# NOT.net
KiCad netlist of a schematic drawn in EAGLE
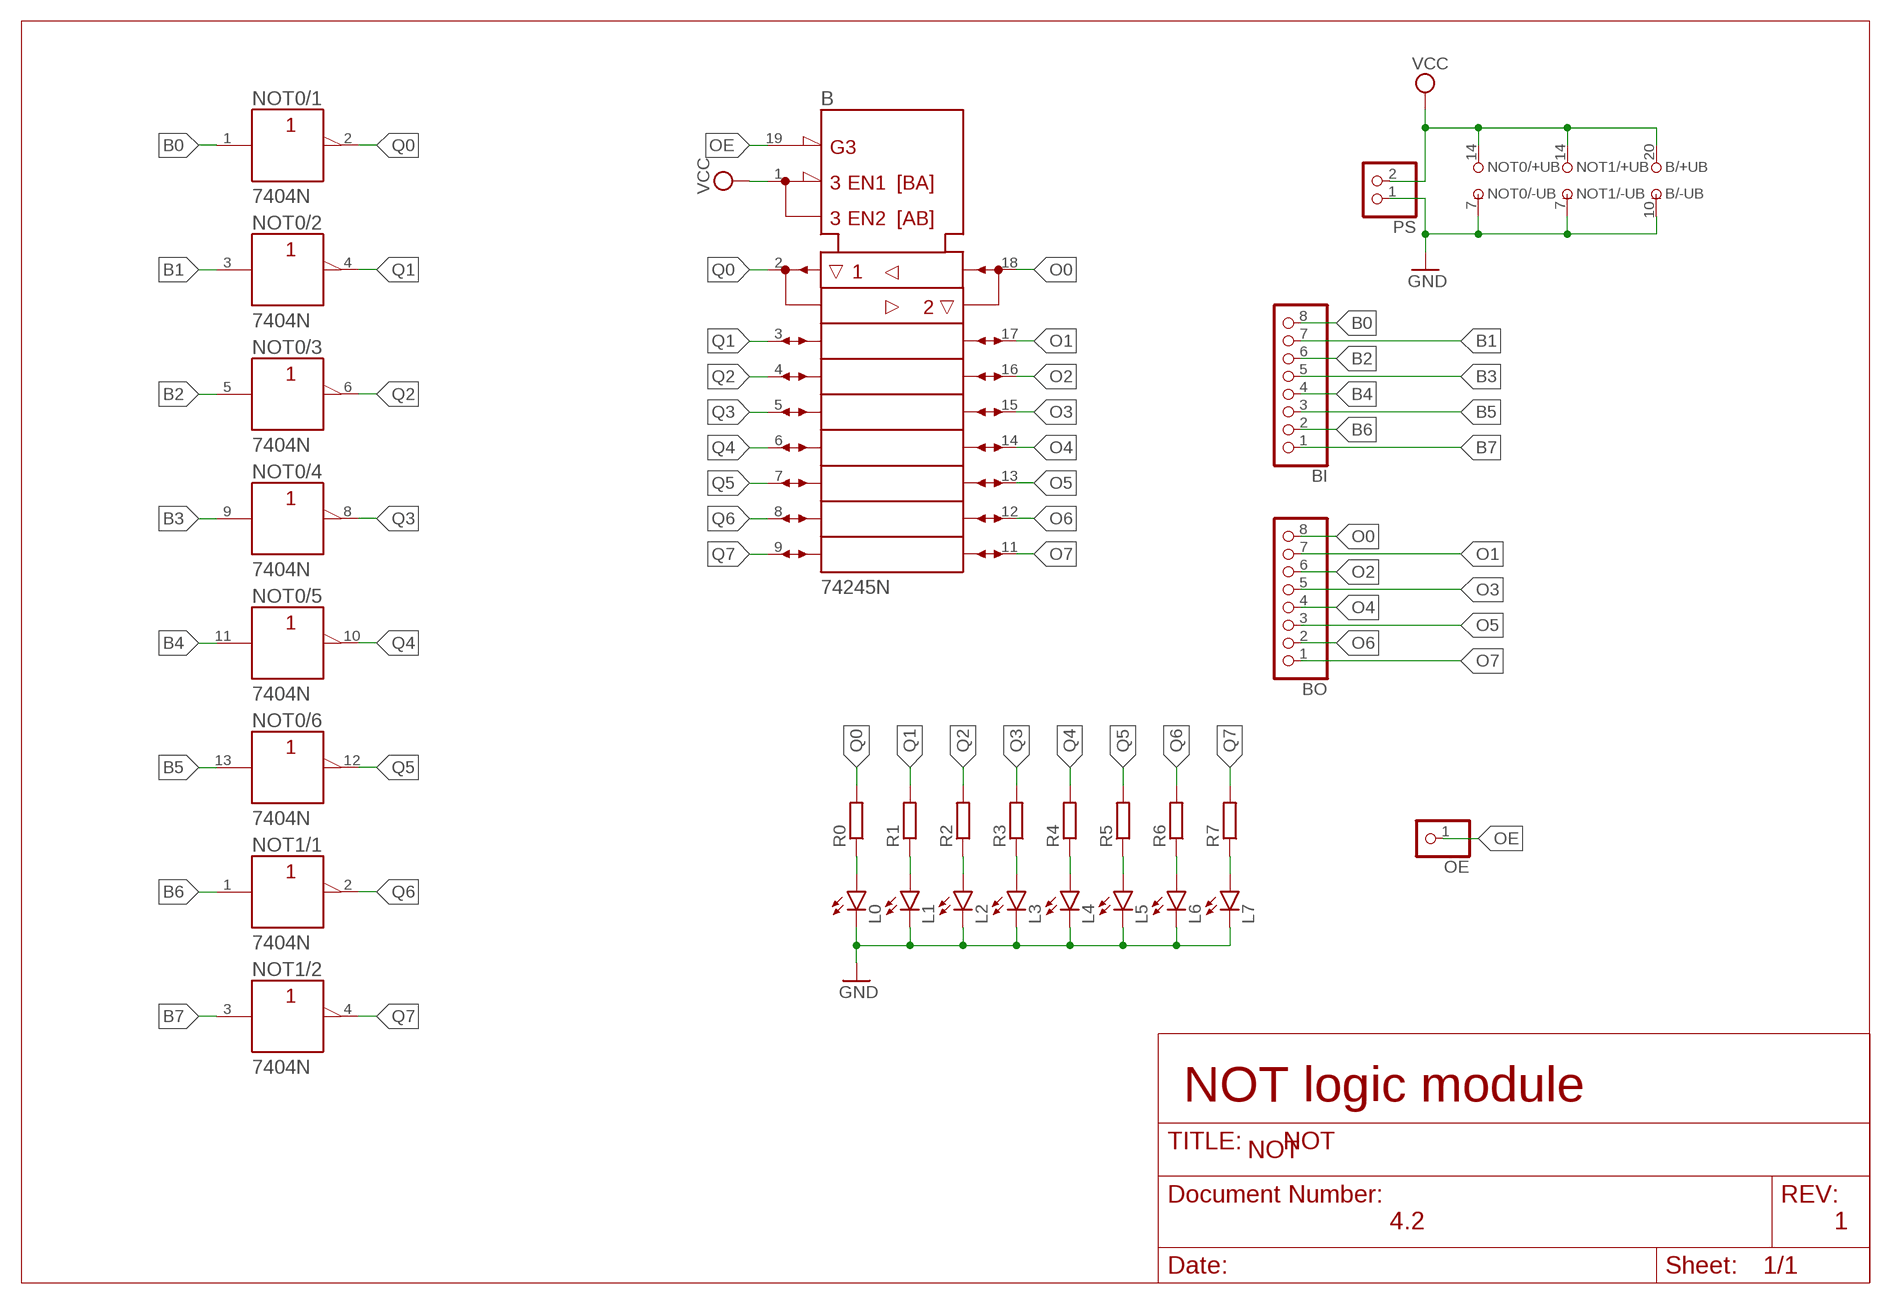
[diagram p0: schematic, sheet 1]

(export (version "E")
  (design (tool "Eeschema 10.0.6"))
  (components
    (comp (ref "B")
      (value "74245N")
      (footprint "eagle-import:DIL20")
      (libsource (lib "eagle-import") (part "74245N"))
    )
    (comp (ref "BI")
      (value "PINHD-1X8")
      (footprint "eagle-import:1X08")
      (libsource (lib "eagle-import") (part "PINHD-1X8"))
    )
    (comp (ref "BO")
      (value "PINHD-1X8")
      (footprint "eagle-import:1X08")
      (libsource (lib "eagle-import") (part "PINHD-1X8"))
    )
    (comp (ref "L0")
      (value "LED5MM")
      (footprint "eagle-import:LED5MM")
      (libsource (lib "eagle-import") (part "LED5MM"))
    )
    (comp (ref "L1")
      (value "LED5MM")
      (footprint "eagle-import:LED5MM")
      (libsource (lib "eagle-import") (part "LED5MM"))
    )
    (comp (ref "L2")
      (value "LED5MM")
      (footprint "eagle-import:LED5MM")
      (libsource (lib "eagle-import") (part "LED5MM"))
    )
    (comp (ref "L3")
      (value "LED5MM")
      (footprint "eagle-import:LED5MM")
      (libsource (lib "eagle-import") (part "LED5MM"))
    )
    (comp (ref "L4")
      (value "LED5MM")
      (footprint "eagle-import:LED5MM")
      (libsource (lib "eagle-import") (part "LED5MM"))
    )
    (comp (ref "L5")
      (value "LED5MM")
      (footprint "eagle-import:LED5MM")
      (libsource (lib "eagle-import") (part "LED5MM"))
    )
    (comp (ref "L6")
      (value "LED5MM")
      (footprint "eagle-import:LED5MM")
      (libsource (lib "eagle-import") (part "LED5MM"))
    )
    (comp (ref "L7")
      (value "LED5MM")
      (footprint "eagle-import:LED5MM")
      (libsource (lib "eagle-import") (part "LED5MM"))
    )
    (comp (ref "NOT0")
      (value "7404N")
      (footprint "eagle-import:DIL14")
      (libsource (lib "eagle-import") (part "7404N"))
    )
    (comp (ref "NOT1")
      (value "7404N")
      (footprint "eagle-import:DIL14")
      (libsource (lib "eagle-import") (part "7404N"))
    )
    (comp (ref "OE")
      (value "PINHD-1X1")
      (footprint "eagle-import:1X01")
      (libsource (lib "eagle-import") (part "PINHD-1X1"))
    )
    (comp (ref "PS")
      (value "PINHD-1X2")
      (footprint "eagle-import:1X02")
      (libsource (lib "eagle-import") (part "PINHD-1X2"))
    )
    (comp (ref "R0")
      (value "R-EU_0204/7")
      (footprint "eagle-import:0204_7")
      (libsource (lib "eagle-import") (part "R-EU_0204/7"))
    )
    (comp (ref "R1")
      (value "R-EU_0204/7")
      (footprint "eagle-import:0204_7")
      (libsource (lib "eagle-import") (part "R-EU_0204/7"))
    )
    (comp (ref "R2")
      (value "R-EU_0204/7")
      (footprint "eagle-import:0204_7")
      (libsource (lib "eagle-import") (part "R-EU_0204/7"))
    )
    (comp (ref "R3")
      (value "R-EU_0204/7")
      (footprint "eagle-import:0204_7")
      (libsource (lib "eagle-import") (part "R-EU_0204/7"))
    )
    (comp (ref "R4")
      (value "R-EU_0204/7")
      (footprint "eagle-import:0204_7")
      (libsource (lib "eagle-import") (part "R-EU_0204/7"))
    )
    (comp (ref "R5")
      (value "R-EU_0204/7")
      (footprint "eagle-import:0204_7")
      (libsource (lib "eagle-import") (part "R-EU_0204/7"))
    )
    (comp (ref "R6")
      (value "R-EU_0204/7")
      (footprint "eagle-import:0204_7")
      (libsource (lib "eagle-import") (part "R-EU_0204/7"))
    )
    (comp (ref "R7")
      (value "R-EU_0204/7")
      (footprint "eagle-import:0204_7")
      (libsource (lib "eagle-import") (part "R-EU_0204/7"))
    )
  )
  (nets
    (net (code "1") (name "B0") (class "Default")
      (node (ref "BI") (pin "8") (pinfunction "8_8") (pintype "passive"))
      (node (ref "NOT0") (pin "1") (pinfunction "A_1") (pintype "input"))
    )
    (net (code "2") (name "B1") (class "Default")
      (node (ref "BI") (pin "7") (pinfunction "7_7") (pintype "passive"))
      (node (ref "NOT0") (pin "3") (pinfunction "A_3") (pintype "input"))
    )
    (net (code "3") (name "B2") (class "Default")
      (node (ref "BI") (pin "6") (pinfunction "6_6") (pintype "passive"))
      (node (ref "NOT0") (pin "5") (pinfunction "A_5") (pintype "input"))
    )
    (net (code "4") (name "B3") (class "Default")
      (node (ref "BI") (pin "5") (pinfunction "5_5") (pintype "passive"))
      (node (ref "NOT0") (pin "9") (pinfunction "A_9") (pintype "input"))
    )
    (net (code "5") (name "B4") (class "Default")
      (node (ref "BI") (pin "4") (pinfunction "4_4") (pintype "passive"))
      (node (ref "NOT0") (pin "11") (pinfunction "A_11") (pintype "input"))
    )
    (net (code "6") (name "B5") (class "Default")
      (node (ref "BI") (pin "3") (pinfunction "3_3") (pintype "passive"))
      (node (ref "NOT0") (pin "13") (pinfunction "A_13") (pintype "input"))
    )
    (net (code "7") (name "B6") (class "Default")
      (node (ref "BI") (pin "2") (pinfunction "2_2") (pintype "passive"))
      (node (ref "NOT1") (pin "1") (pinfunction "A_1") (pintype "input"))
    )
    (net (code "8") (name "B7") (class "Default")
      (node (ref "BI") (pin "1") (pinfunction "1_1") (pintype "passive"))
      (node (ref "NOT1") (pin "3") (pinfunction "A_3") (pintype "input"))
    )
    (net (code "9") (name "GND") (class "Default")
      (node (ref "B") (pin "10") (pinfunction "-UB_10") (pintype "power_in"))
      (node (ref "L0") (pin "K") (pinfunction "C_K") (pintype "passive"))
      (node (ref "L1") (pin "K") (pinfunction "C_K") (pintype "passive"))
      (node (ref "L2") (pin "K") (pinfunction "C_K") (pintype "passive"))
      (node (ref "L3") (pin "K") (pinfunction "C_K") (pintype "passive"))
      (node (ref "L4") (pin "K") (pinfunction "C_K") (pintype "passive"))
      (node (ref "L5") (pin "K") (pinfunction "C_K") (pintype "passive"))
      (node (ref "L6") (pin "K") (pinfunction "C_K") (pintype "passive"))
      (node (ref "L7") (pin "K") (pinfunction "C_K") (pintype "passive"))
      (node (ref "NOT0") (pin "7") (pinfunction "-UB_7") (pintype "power_in"))
      (node (ref "NOT1") (pin "7") (pinfunction "-UB_7") (pintype "power_in"))
      (node (ref "PS") (pin "1") (pinfunction "1_1") (pintype "passive"))
    )
    (net (code "10") (name "Net-(L0-PadA)") (class "Default")
      (node (ref "L0") (pin "A") (pinfunction "A_A") (pintype "passive"))
      (node (ref "R0") (pin "1") (pinfunction "1_1") (pintype "passive"))
    )
    (net (code "11") (name "Net-(L1-PadA)") (class "Default")
      (node (ref "L1") (pin "A") (pinfunction "A_A") (pintype "passive"))
      (node (ref "R1") (pin "1") (pinfunction "1_1") (pintype "passive"))
    )
    (net (code "12") (name "Net-(L2-PadA)") (class "Default")
      (node (ref "L2") (pin "A") (pinfunction "A_A") (pintype "passive"))
      (node (ref "R2") (pin "1") (pinfunction "1_1") (pintype "passive"))
    )
    (net (code "13") (name "Net-(L3-PadA)") (class "Default")
      (node (ref "L3") (pin "A") (pinfunction "A_A") (pintype "passive"))
      (node (ref "R3") (pin "1") (pinfunction "1_1") (pintype "passive"))
    )
    (net (code "14") (name "Net-(L4-PadA)") (class "Default")
      (node (ref "L4") (pin "A") (pinfunction "A_A") (pintype "passive"))
      (node (ref "R4") (pin "1") (pinfunction "1_1") (pintype "passive"))
    )
    (net (code "15") (name "Net-(L5-PadA)") (class "Default")
      (node (ref "L5") (pin "A") (pinfunction "A_A") (pintype "passive"))
      (node (ref "R5") (pin "1") (pinfunction "1_1") (pintype "passive"))
    )
    (net (code "16") (name "Net-(L6-PadA)") (class "Default")
      (node (ref "L6") (pin "A") (pinfunction "A_A") (pintype "passive"))
      (node (ref "R6") (pin "1") (pinfunction "1_1") (pintype "passive"))
    )
    (net (code "17") (name "Net-(L7-PadA)") (class "Default")
      (node (ref "L7") (pin "A") (pinfunction "A_A") (pintype "passive"))
      (node (ref "R7") (pin "1") (pinfunction "1_1") (pintype "passive"))
    )
    (net (code "18") (name "O0") (class "Default")
      (node (ref "B") (pin "18") (pinfunction "B1_18") (pintype "bidirectional"))
      (node (ref "BO") (pin "8") (pinfunction "8_8") (pintype "passive"))
    )
    (net (code "19") (name "O1") (class "Default")
      (node (ref "B") (pin "17") (pinfunction "B2_17") (pintype "bidirectional"))
      (node (ref "BO") (pin "7") (pinfunction "7_7") (pintype "passive"))
    )
    (net (code "20") (name "O2") (class "Default")
      (node (ref "B") (pin "16") (pinfunction "B3_16") (pintype "bidirectional"))
      (node (ref "BO") (pin "6") (pinfunction "6_6") (pintype "passive"))
    )
    (net (code "21") (name "O3") (class "Default")
      (node (ref "B") (pin "15") (pinfunction "B4_15") (pintype "bidirectional"))
      (node (ref "BO") (pin "5") (pinfunction "5_5") (pintype "passive"))
    )
    (net (code "22") (name "O4") (class "Default")
      (node (ref "B") (pin "14") (pinfunction "B5_14") (pintype "bidirectional"))
      (node (ref "BO") (pin "4") (pinfunction "4_4") (pintype "passive"))
    )
    (net (code "23") (name "O5") (class "Default")
      (node (ref "B") (pin "13") (pinfunction "B6_13") (pintype "bidirectional"))
      (node (ref "BO") (pin "3") (pinfunction "3_3") (pintype "passive"))
    )
    (net (code "24") (name "O6") (class "Default")
      (node (ref "B") (pin "12") (pinfunction "B7_12") (pintype "bidirectional"))
      (node (ref "BO") (pin "2") (pinfunction "2_2") (pintype "passive"))
    )
    (net (code "25") (name "O7") (class "Default")
      (node (ref "B") (pin "11") (pinfunction "B8_11") (pintype "bidirectional"))
      (node (ref "BO") (pin "1") (pinfunction "1_1") (pintype "passive"))
    )
    (net (code "26") (name "OE") (class "Default")
      (node (ref "B") (pin "19") (pinfunction "~{G}_19") (pintype "input"))
      (node (ref "OE") (pin "1") (pinfunction "1_1") (pintype "passive"))
    )
    (net (code "27") (name "Q0") (class "Default")
      (node (ref "B") (pin "2") (pinfunction "A1_2") (pintype "bidirectional"))
      (node (ref "NOT0") (pin "2") (pinfunction "Y_2") (pintype "output"))
      (node (ref "R0") (pin "2") (pinfunction "2_2") (pintype "passive"))
    )
    (net (code "28") (name "Q1") (class "Default")
      (node (ref "B") (pin "3") (pinfunction "A2_3") (pintype "bidirectional"))
      (node (ref "NOT0") (pin "4") (pinfunction "Y_4") (pintype "output"))
      (node (ref "R1") (pin "2") (pinfunction "2_2") (pintype "passive"))
    )
    (net (code "29") (name "Q2") (class "Default")
      (node (ref "B") (pin "4") (pinfunction "A3_4") (pintype "bidirectional"))
      (node (ref "NOT0") (pin "6") (pinfunction "Y_6") (pintype "output"))
      (node (ref "R2") (pin "2") (pinfunction "2_2") (pintype "passive"))
    )
    (net (code "30") (name "Q3") (class "Default")
      (node (ref "B") (pin "5") (pinfunction "A4_5") (pintype "bidirectional"))
      (node (ref "NOT0") (pin "8") (pinfunction "Y_8") (pintype "output"))
      (node (ref "R3") (pin "2") (pinfunction "2_2") (pintype "passive"))
    )
    (net (code "31") (name "Q4") (class "Default")
      (node (ref "B") (pin "6") (pinfunction "A5_6") (pintype "bidirectional"))
      (node (ref "NOT0") (pin "10") (pinfunction "Y_10") (pintype "output"))
      (node (ref "R4") (pin "2") (pinfunction "2_2") (pintype "passive"))
    )
    (net (code "32") (name "Q5") (class "Default")
      (node (ref "B") (pin "7") (pinfunction "A6_7") (pintype "bidirectional"))
      (node (ref "NOT0") (pin "12") (pinfunction "Y_12") (pintype "output"))
      (node (ref "R5") (pin "2") (pinfunction "2_2") (pintype "passive"))
    )
    (net (code "33") (name "Q6") (class "Default")
      (node (ref "B") (pin "8") (pinfunction "A7_8") (pintype "bidirectional"))
      (node (ref "NOT1") (pin "2") (pinfunction "Y_2") (pintype "output"))
      (node (ref "R6") (pin "2") (pinfunction "2_2") (pintype "passive"))
    )
    (net (code "34") (name "Q7") (class "Default")
      (node (ref "B") (pin "9") (pinfunction "A8_9") (pintype "bidirectional"))
      (node (ref "NOT1") (pin "4") (pinfunction "Y_4") (pintype "output"))
      (node (ref "R7") (pin "2") (pinfunction "2_2") (pintype "passive"))
    )
    (net (code "35") (name "VCC") (class "Default")
      (node (ref "B") (pin "1") (pinfunction "DIR_1") (pintype "input"))
      (node (ref "B") (pin "20") (pinfunction "+UB_20") (pintype "power_in"))
      (node (ref "NOT0") (pin "14") (pinfunction "+UB_14") (pintype "power_in"))
      (node (ref "NOT1") (pin "14") (pinfunction "+UB_14") (pintype "power_in"))
      (node (ref "PS") (pin "2") (pinfunction "2_2") (pintype "passive"))
    )
  )
)
